# BARBAROV_Power_Distrubution_Board.net
KiCad netlist of a schematic drawn in Altium Designer
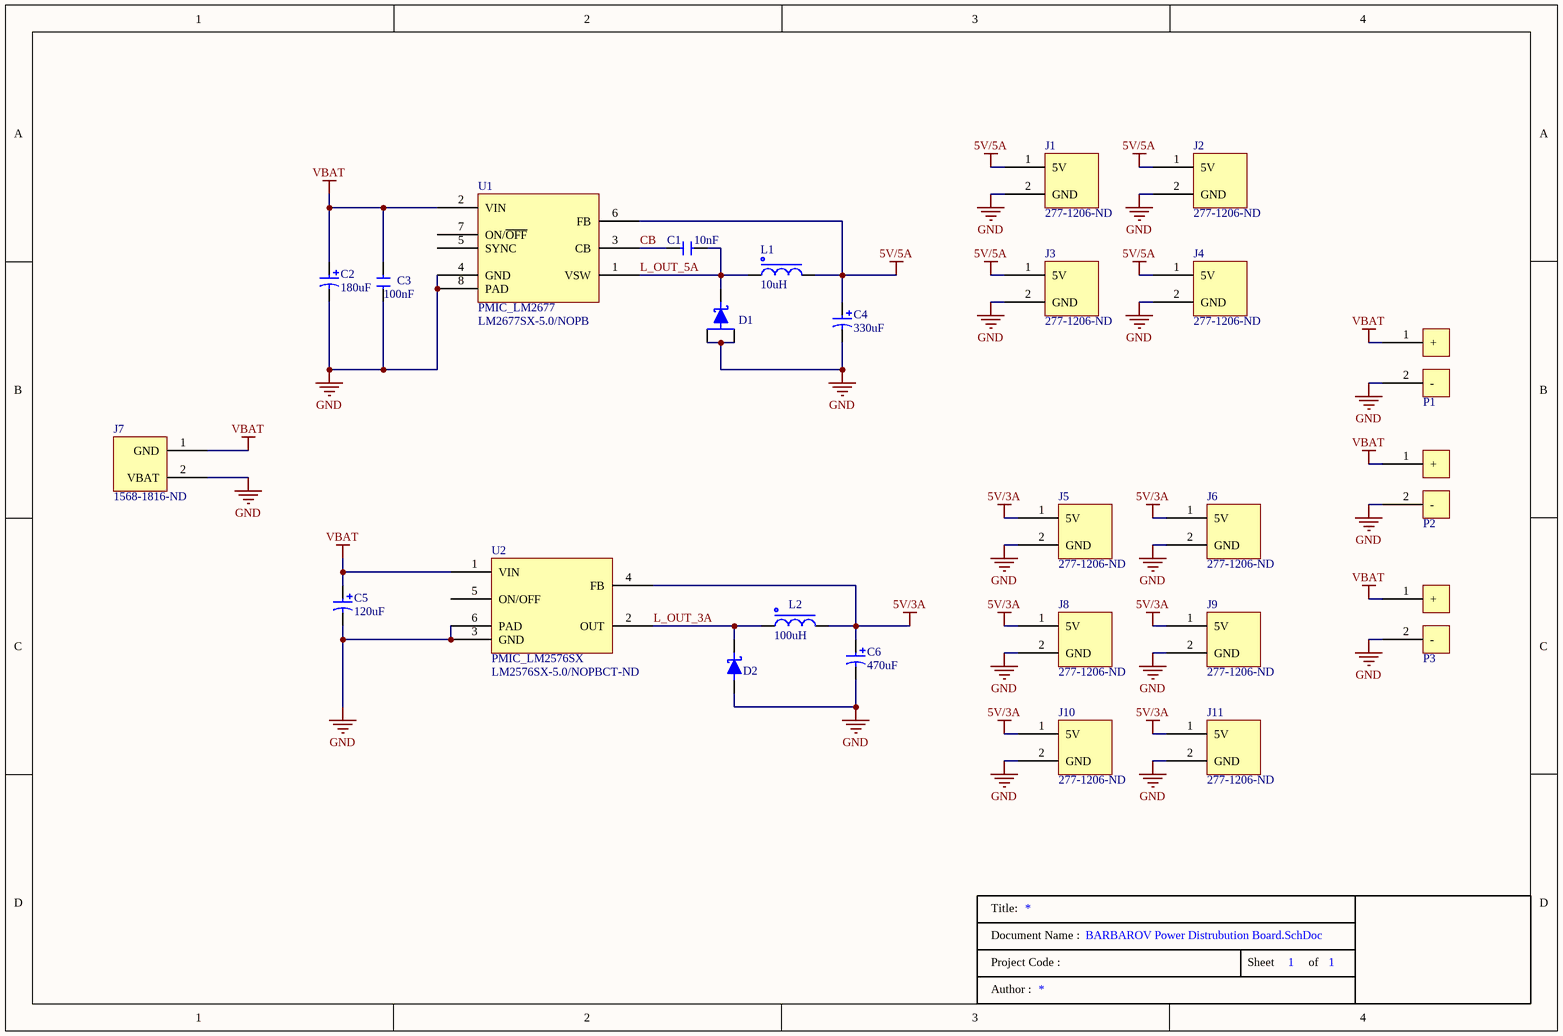
[diagram p0: BARBAROV Power Distrubution Board.SchDoc]

(export (version "E")
  (design (tool "Eeschema 10.0.6"))
  (components
    (comp (ref "C1")
      (value "CAP_10nF_%10_50V_0805_X7R_CER")
      (footprint "0805_CAP")
      (description "CAP CER 10000PF 50V X7R 0805")
      (fields
        (field (name "MANUFACTURER") "Samsung")
        (field (name "MANUFACTURER PART NUMBER") "CL21B103KBANNNC")
        (field (name "CAPACITANCE") "10nF")
      )
      (libsource (lib "Main Component Library") (part "CAP_10nF_%10_50V_0805_X7R_CER"))
    )
    (comp (ref "C2")
      (value "CAP_180uF_20%_25V_SMD_ALUM POLY_8.30mmx8.30mm")
      (footprint "RADIAL-2_8.30MMX8.30MM_PANASONIC")
      (description "Cap Aluminum Polymer 180uF 25V 20% Cylindrical 16m Ohm 1470mA 2000 hr 125°C Emboss T/R")
      (fields
        (field (name "MANUFACTURER") "Panasonic")
        (field (name "MANUFACTURER PART NUMBER") "25SVT180M")
        (field (name "CAPACITANCE") "180uF")
      )
      (libsource (lib "Main Component Library") (part "CAP_180uF_20%_25V_SMD_ALUM POLY_8.30mmx8.30mm"))
    )
    (comp (ref "C3")
      (value "CAP_100nF_50V_0805_C0G_CER")
      (footprint "0805_CAP")
      (description "Cap Ceramic 0.1uF 50V X7R 20% SMD 0805 125C Paper T/R")
      (fields
        (field (name "MANUFACTURER") "KEMET")
        (field (name "MANUFACTURER PART NUMBER") "C0805C104M5RACTU")
        (field (name "CAPACITANCE") "100nF")
      )
      (libsource (lib "Main Component Library") (part "CAP_100nF_50V_0805_C0G_CER"))
    )
    (comp (ref "C4")
      (value "CAP_330uF_20%_16V_SMD_ALUM POLY_8.30mm x 8.30mm")
      (footprint "RADIAL-2_8.30MMX8.30MM_PANASONIC")
      (description "Cap Alum Poly 330UF 20% 16V SMD")
      (fields
        (field (name "MANUFACTURER") "Wurth Electronics")
        (field (name "MANUFACTURER PART NUMBER") "875075355004")
        (field (name "CAPACITANCE") "330uF")
      )
      (libsource (lib "Main Component Library") (part "CAP_330uF_20%_16V_SMD_ALUM POLY_8.30mm x 8.30mm"))
    )
    (comp (ref "C5")
      (value "CAP_120uF_20%_20V_ALUM POLY_SMD")
      (footprint "CAP_6SVPC330M")
      (description "Cap Aluminum Polymer 120uF 20VDC 20%( 6.3 X 5.9mm) SMD 0.025 Ohm 3200mA 5000h 105C T/R")
      (fields
        (field (name "MANUFACTURER") "Panasonic")
        (field (name "MANUFACTURER PART NUMBER") "20SVPF120M")
        (field (name "CAPACITANCE") "120uF")
      )
      (libsource (lib "Main Schematic Library") (part "CAP_120uF_20%_20V_ALUM POLY_SMD"))
    )
    (comp (ref "C6")
      (value "CAP_470uF_20%_16V_SMD_ALUM")
      (footprint "CAP_EEVTG1C471Q")
      (description "贴片铝电解电容 470uF ±20% 16V 0.12Ω 2000hrs@125°C AEC_D12.5x13.5mm_SM")
      (fields
        (field (name "MANUFACTURER") "Panasonic")
        (field (name "MANUFACTURER PART NUMBER") "EEV-TG1C471Q")
        (field (name "CAPACITANCE") "470uF")
      )
      (libsource (lib "Main Schematic Library") (part "CAP_470uF_20%_16V_SMD_ALUM"))
    )
    (comp (ref "D1")
      (value "DIODE_SCHOTTKY_200V_10A_DPAK")
      (footprint "3PIN_DPAK_DIODE")
      (description "Diode Schottky 200V 10A Dpak")
      (fields
        (field (name "MANUFACTURER") "Sangdest Microelectronics")
        (field (name "MANUFACTURER PART NUMBER") "SBRD10200")
      )
      (libsource (lib "Main Component Library") (part "DIODE_SCHOTTKY_200V_10A_DPAK"))
    )
    (comp (ref "D2")
      (value "DIODE_SCHOTTKY_20V_4A_DO214AB")
      (footprint "DIOM6959X25M")
      (description "SL42 Series 20 V 2 A Surface Mount Schottky Barrier Rectifier - DO-214AB (SMC)")
      (fields
        (field (name "MANUFACTURER") "Vishay Semiconductors")
        (field (name "MANUFACTURER PART NUMBER") "SL42-E3/57T")
      )
      (libsource (lib "Main Schematic Library") (part "DIODE SCHOTTKY 20V 4A DO214AB"))
    )
    (comp (ref "J1")
      (value "CONN_TERM BLOCK_HDR_2POS_VERT_3.81MM")
      (footprint "CONN TERM BLOCK HDR 2POS 90DEG 3.81MM")
      (fields
        (field (name "MANUFACTURER") "Phoenix Contact")
        (field (name "MANUFACTURER PART NUMBER") "1803277")
        (field (name "VOLTAGE") "300V")
        (field (name "SUPPLIER PART NUMBER 1") "277-1206-ND")
      )
      (libsource (lib "Main Component Library") (part "CONN_TERM BLOCK_HDR_2POS_VERT_3.81MM"))
    )
    (comp (ref "J2")
      (value "CONN_TERM BLOCK_HDR_2POS_VERT_3.81MM")
      (footprint "CONN TERM BLOCK HDR 2POS 90DEG 3.81MM")
      (fields
        (field (name "MANUFACTURER") "Phoenix Contact")
        (field (name "MANUFACTURER PART NUMBER") "1803277")
        (field (name "VOLTAGE") "300V")
        (field (name "SUPPLIER PART NUMBER 1") "277-1206-ND")
      )
      (libsource (lib "Main Component Library") (part "CONN_TERM BLOCK_HDR_2POS_VERT_3.81MM"))
    )
    (comp (ref "J3")
      (value "CONN_TERM BLOCK_HDR_2POS_VERT_3.81MM")
      (footprint "CONN TERM BLOCK HDR 2POS 90DEG 3.81MM")
      (fields
        (field (name "MANUFACTURER") "Phoenix Contact")
        (field (name "MANUFACTURER PART NUMBER") "1803277")
        (field (name "VOLTAGE") "300V")
        (field (name "SUPPLIER PART NUMBER 1") "277-1206-ND")
      )
      (libsource (lib "Main Component Library") (part "CONN_TERM BLOCK_HDR_2POS_VERT_3.81MM"))
    )
    (comp (ref "J4")
      (value "CONN_TERM BLOCK_HDR_2POS_VERT_3.81MM")
      (footprint "CONN TERM BLOCK HDR 2POS 90DEG 3.81MM")
      (fields
        (field (name "MANUFACTURER") "Phoenix Contact")
        (field (name "MANUFACTURER PART NUMBER") "1803277")
        (field (name "VOLTAGE") "300V")
        (field (name "SUPPLIER PART NUMBER 1") "277-1206-ND")
      )
      (libsource (lib "Main Component Library") (part "CONN_TERM BLOCK_HDR_2POS_VERT_3.81MM"))
    )
    (comp (ref "J5")
      (value "CONN_TERM BLOCK_HDR_2POS_VERT_3.81MM")
      (footprint "CONN TERM BLOCK HDR 2POS 90DEG 3.81MM")
      (fields
        (field (name "MANUFACTURER") "Phoenix Contact")
        (field (name "MANUFACTURER PART NUMBER") "1803277")
        (field (name "VOLTAGE") "300V")
        (field (name "SUPPLIER PART NUMBER 1") "277-1206-ND")
      )
      (libsource (lib "Main Component Library") (part "CONN_TERM BLOCK_HDR_2POS_VERT_3.81MM"))
    )
    (comp (ref "J6")
      (value "CONN_TERM BLOCK_HDR_2POS_VERT_3.81MM")
      (footprint "CONN TERM BLOCK HDR 2POS 90DEG 3.81MM")
      (fields
        (field (name "MANUFACTURER") "Phoenix Contact")
        (field (name "MANUFACTURER PART NUMBER") "1803277")
        (field (name "VOLTAGE") "300V")
        (field (name "SUPPLIER PART NUMBER 1") "277-1206-ND")
      )
      (libsource (lib "Main Component Library") (part "CONN_TERM BLOCK_HDR_2POS_VERT_3.81MM"))
    )
    (comp (ref "J7")
      (value "CONN_XT60")
      (footprint "XT60_CONN")
      (description "XT60 Connectors Male/female Pair")
      (fields
        (field (name "MANUFACTURER") "SparkFun")
        (field (name "MANUFACTURER PART NUMBER") "PRT-10474")
        (field (name "SUPPLIER PART NUMBER 1") "1568-1816-ND")
      )
      (libsource (lib "Main Schematic Library") (part "CONN_XT60"))
    )
    (comp (ref "J8")
      (value "CONN_TERM BLOCK_HDR_2POS_VERT_3.81MM")
      (footprint "CONN TERM BLOCK HDR 2POS 90DEG 3.81MM")
      (fields
        (field (name "MANUFACTURER") "Phoenix Contact")
        (field (name "MANUFACTURER PART NUMBER") "1803277")
        (field (name "VOLTAGE") "300V")
        (field (name "SUPPLIER PART NUMBER 1") "277-1206-ND")
      )
      (libsource (lib "Main Component Library") (part "CONN_TERM BLOCK_HDR_2POS_VERT_3.81MM"))
    )
    (comp (ref "J9")
      (value "CONN_TERM BLOCK_HDR_2POS_VERT_3.81MM")
      (footprint "CONN TERM BLOCK HDR 2POS 90DEG 3.81MM")
      (fields
        (field (name "MANUFACTURER") "Phoenix Contact")
        (field (name "MANUFACTURER PART NUMBER") "1803277")
        (field (name "VOLTAGE") "300V")
        (field (name "SUPPLIER PART NUMBER 1") "277-1206-ND")
      )
      (libsource (lib "Main Component Library") (part "CONN_TERM BLOCK_HDR_2POS_VERT_3.81MM"))
    )
    (comp (ref "J10")
      (value "CONN_TERM BLOCK_HDR_2POS_VERT_3.81MM")
      (footprint "CONN TERM BLOCK HDR 2POS 90DEG 3.81MM")
      (fields
        (field (name "MANUFACTURER") "Phoenix Contact")
        (field (name "MANUFACTURER PART NUMBER") "1803277")
        (field (name "VOLTAGE") "300V")
        (field (name "SUPPLIER PART NUMBER 1") "277-1206-ND")
      )
      (libsource (lib "Main Component Library") (part "CONN_TERM BLOCK_HDR_2POS_VERT_3.81MM"))
    )
    (comp (ref "J11")
      (value "CONN_TERM BLOCK_HDR_2POS_VERT_3.81MM")
      (footprint "CONN TERM BLOCK HDR 2POS 90DEG 3.81MM")
      (fields
        (field (name "MANUFACTURER") "Phoenix Contact")
        (field (name "MANUFACTURER PART NUMBER") "1803277")
        (field (name "VOLTAGE") "300V")
        (field (name "SUPPLIER PART NUMBER 1") "277-1206-ND")
      )
      (libsource (lib "Main Component Library") (part "CONN_TERM BLOCK_HDR_2POS_VERT_3.81MM"))
    )
    (comp (ref "L1")
      (value "IND_10uH_10A_16.8MOHM_SMD")
      (footprint "IND13.70MM13.70MMX7MM")
      (description "Inductor Power Shielded Wirewound 10uH 20% 100KHz Iron 10A 0.0168Ohm DCR T/R")
      (fields
        (field (name "MANUFACTURER") "Bourns")
        (field (name "MANUFACTURER PART NUMBER") "SRP1270-100M")
        (field (name "INDUCTANCE") "10uH")
      )
      (libsource (lib "Main Component Library") (part "IND_10uH_10A_16.8MOHM_SMD"))
    )
    (comp (ref "L2")
      (value "IND_100uH_9.1A_39.4MOHM_SM")
      (footprint "SMD_IND_22.48MMX22.00MM")
      (description "Inductor Power Shielded Wirewound 100uH 20% 100KHz Powdered Iron 9.1A 0.0394Ohm DCR 8787 T/R")
      (fields
        (field (name "MANUFACTURER") "Vishay Dale")
        (field (name "MANUFACTURER PART NUMBER") "IHLP8787MZER101M51")
        (field (name "INDUCTANCE") "100uH")
      )
      (libsource (lib "Main Component Library") (part "IND_100uH_9.1A_39.4MOHM_SM"))
    )
    (comp (ref "P1")
      (value "ESC_PAD")
      (footprint "ESC_SOLDER_PAD")
      (libsource (lib "Main Component Library") (part "ESC_PAD"))
    )
    (comp (ref "P2")
      (value "ESC_PAD")
      (footprint "ESC_SOLDER_PAD")
      (libsource (lib "Main Component Library") (part "ESC_PAD"))
    )
    (comp (ref "P3")
      (value "ESC_PAD")
      (footprint "ESC_SOLDER_PAD")
      (libsource (lib "Main Component Library") (part "ESC_PAD"))
    )
    (comp (ref "U1")
      (value "PMIC_LM2677")
      (footprint "DPAK127P1435X464-8M")
      (description "SIMPLE SWITCHE High Efficiency 5A Step-Down Voltage egulator with Sync 7-DDPAK/TO-263 -40 to 125")
      (fields
        (field (name "MANUFACTURER") "TI National Semiconductor")
        (field (name "MANUFACTURER PART NUMBER") "LM2677SX-5.0/NOPB")
      )
      (libsource (lib "Main Component Library") (part "PMIC_LM2677"))
    )
    (comp (ref "U2")
      (value "PMIC_LM2576SX")
      (footprint "TO-263-6/DDPAK")
      (description "IC REG BUCK 5V 3A TO263-5")
      (fields
        (field (name "MANUFACTURER") "TI National Semiconductor")
        (field (name "MANUFACTURER PART NUMBER") "LM2576SX-5.0/NOPB")
        (field (name "SUPPLIER PART NUMBER 1") "LM2576SX-5.0/NOPBCT-ND")
      )
      (libsource (lib "Main Component Library") (part "PMIC_LM2576SX"))
    )
  )
  (nets
    (net (code "1") (name "/CB") (class "Default")
      (node (ref "C1") (pin "1") (pinfunction "1_1") (pintype "passive"))
      (node (ref "U1") (pin "3") (pinfunction "CB_3") (pintype "passive"))
    )
    (net (code "2") (name "/L_OUT_3A") (class "Default")
      (node (ref "D2") (pin "2") (pinfunction "CATHODE_2") (pintype "passive"))
      (node (ref "L2") (pin "1") (pinfunction "1_1") (pintype "passive"))
      (node (ref "U2") (pin "2") (pinfunction "OUT_2") (pintype "passive"))
    )
    (net (code "3") (name "/L_OUT_5A") (class "Default")
      (node (ref "C1") (pin "2") (pinfunction "2_2") (pintype "passive"))
      (node (ref "D1") (pin "2") (pinfunction "CATHODE_2") (pintype "passive"))
      (node (ref "L1") (pin "1") (pinfunction "1_1") (pintype "passive"))
      (node (ref "U1") (pin "1") (pinfunction "VSW_1") (pintype "passive"))
    )
    (net (code "4") (name "5V{slash}3A") (class "Default")
      (node (ref "C6") (pin "1") (pinfunction "1_1") (pintype "passive"))
      (node (ref "J10") (pin "1") (pinfunction "5V_1") (pintype "passive"))
      (node (ref "J11") (pin "1") (pinfunction "5V_1") (pintype "passive"))
      (node (ref "J5") (pin "1") (pinfunction "5V_1") (pintype "passive"))
      (node (ref "J6") (pin "1") (pinfunction "5V_1") (pintype "passive"))
      (node (ref "J8") (pin "1") (pinfunction "5V_1") (pintype "passive"))
      (node (ref "J9") (pin "1") (pinfunction "5V_1") (pintype "passive"))
      (node (ref "L2") (pin "2") (pinfunction "2_2") (pintype "passive"))
      (node (ref "U2") (pin "4") (pinfunction "FB_4") (pintype "passive"))
    )
    (net (code "5") (name "5V{slash}5A") (class "Default")
      (node (ref "C4") (pin "1") (pinfunction "1_1") (pintype "passive"))
      (node (ref "J1") (pin "1") (pinfunction "5V_1") (pintype "passive"))
      (node (ref "J2") (pin "1") (pinfunction "5V_1") (pintype "passive"))
      (node (ref "J3") (pin "1") (pinfunction "5V_1") (pintype "passive"))
      (node (ref "J4") (pin "1") (pinfunction "5V_1") (pintype "passive"))
      (node (ref "L1") (pin "2") (pinfunction "2_2") (pintype "passive"))
      (node (ref "U1") (pin "6") (pinfunction "FB_6") (pintype "passive"))
    )
    (net (code "6") (name "GND") (class "Default")
      (node (ref "C2") (pin "2") (pinfunction "2_2") (pintype "passive"))
      (node (ref "C3") (pin "2") (pinfunction "2_2") (pintype "passive"))
      (node (ref "C4") (pin "2") (pinfunction "2_2") (pintype "passive"))
      (node (ref "C5") (pin "2") (pinfunction "2_2") (pintype "passive"))
      (node (ref "C6") (pin "2") (pinfunction "2_2") (pintype "passive"))
      (node (ref "D1") (pin "1") (pinfunction "ANODE_1") (pintype "passive"))
      (node (ref "D1") (pin "3") (pinfunction "ANODE_3") (pintype "passive"))
      (node (ref "D2") (pin "1") (pinfunction "ANODE_1") (pintype "passive"))
      (node (ref "J1") (pin "2") (pinfunction "GND_2") (pintype "passive"))
      (node (ref "J10") (pin "2") (pinfunction "GND_2") (pintype "passive"))
      (node (ref "J11") (pin "2") (pinfunction "GND_2") (pintype "passive"))
      (node (ref "J2") (pin "2") (pinfunction "GND_2") (pintype "passive"))
      (node (ref "J3") (pin "2") (pinfunction "GND_2") (pintype "passive"))
      (node (ref "J4") (pin "2") (pinfunction "GND_2") (pintype "passive"))
      (node (ref "J5") (pin "2") (pinfunction "GND_2") (pintype "passive"))
      (node (ref "J6") (pin "2") (pinfunction "GND_2") (pintype "passive"))
      (node (ref "J7") (pin "2") (pinfunction "VBAT_2") (pintype "passive"))
      (node (ref "J8") (pin "2") (pinfunction "GND_2") (pintype "passive"))
      (node (ref "J9") (pin "2") (pinfunction "GND_2") (pintype "passive"))
      (node (ref "P1") (pin "2") (pinfunction "-_2") (pintype "passive"))
      (node (ref "P2") (pin "2") (pinfunction "-_2") (pintype "passive"))
      (node (ref "P3") (pin "2") (pinfunction "-_2") (pintype "passive"))
      (node (ref "U1") (pin "4") (pinfunction "GND_4") (pintype "passive"))
      (node (ref "U1") (pin "8") (pinfunction "PAD_8") (pintype "passive"))
      (node (ref "U2") (pin "3") (pinfunction "GND_3") (pintype "passive"))
      (node (ref "U2") (pin "6") (pinfunction "PAD_6") (pintype "passive"))
    )
    (net (code "7") (name "VBAT") (class "Default")
      (node (ref "C2") (pin "1") (pinfunction "1_1") (pintype "passive"))
      (node (ref "C3") (pin "1") (pinfunction "1_1") (pintype "passive"))
      (node (ref "C5") (pin "1") (pinfunction "1_1") (pintype "passive"))
      (node (ref "J7") (pin "1") (pinfunction "GND_1") (pintype "passive"))
      (node (ref "P1") (pin "1") (pinfunction "+_1") (pintype "passive"))
      (node (ref "P2") (pin "1") (pinfunction "+_1") (pintype "passive"))
      (node (ref "P3") (pin "1") (pinfunction "+_1") (pintype "passive"))
      (node (ref "U1") (pin "2") (pinfunction "VIN_2") (pintype "passive"))
      (node (ref "U2") (pin "1") (pinfunction "VIN_1") (pintype "passive"))
    )
    (net (code "8") (name "unconnected-(U1-ON{slash}~{OFF}-Pad7)") (class "Default")
      (node (ref "U1") (pin "7") (pinfunction "ON/~{OFF}_7") (pintype "passive"))
    )
    (net (code "9") (name "unconnected-(U1-SYNC-Pad5)") (class "Default")
      (node (ref "U1") (pin "5") (pinfunction "SYNC_5") (pintype "passive"))
    )
    (net (code "10") (name "unconnected-(U2-ON{slash}OFF-Pad5)") (class "Default")
      (node (ref "U2") (pin "5") (pinfunction "ON/OFF_5") (pintype "passive"))
    )
  )
)
